# ir-sensor-breakout-mk-3_0-pth.net
KiCad netlist of a schematic drawn in EAGLE
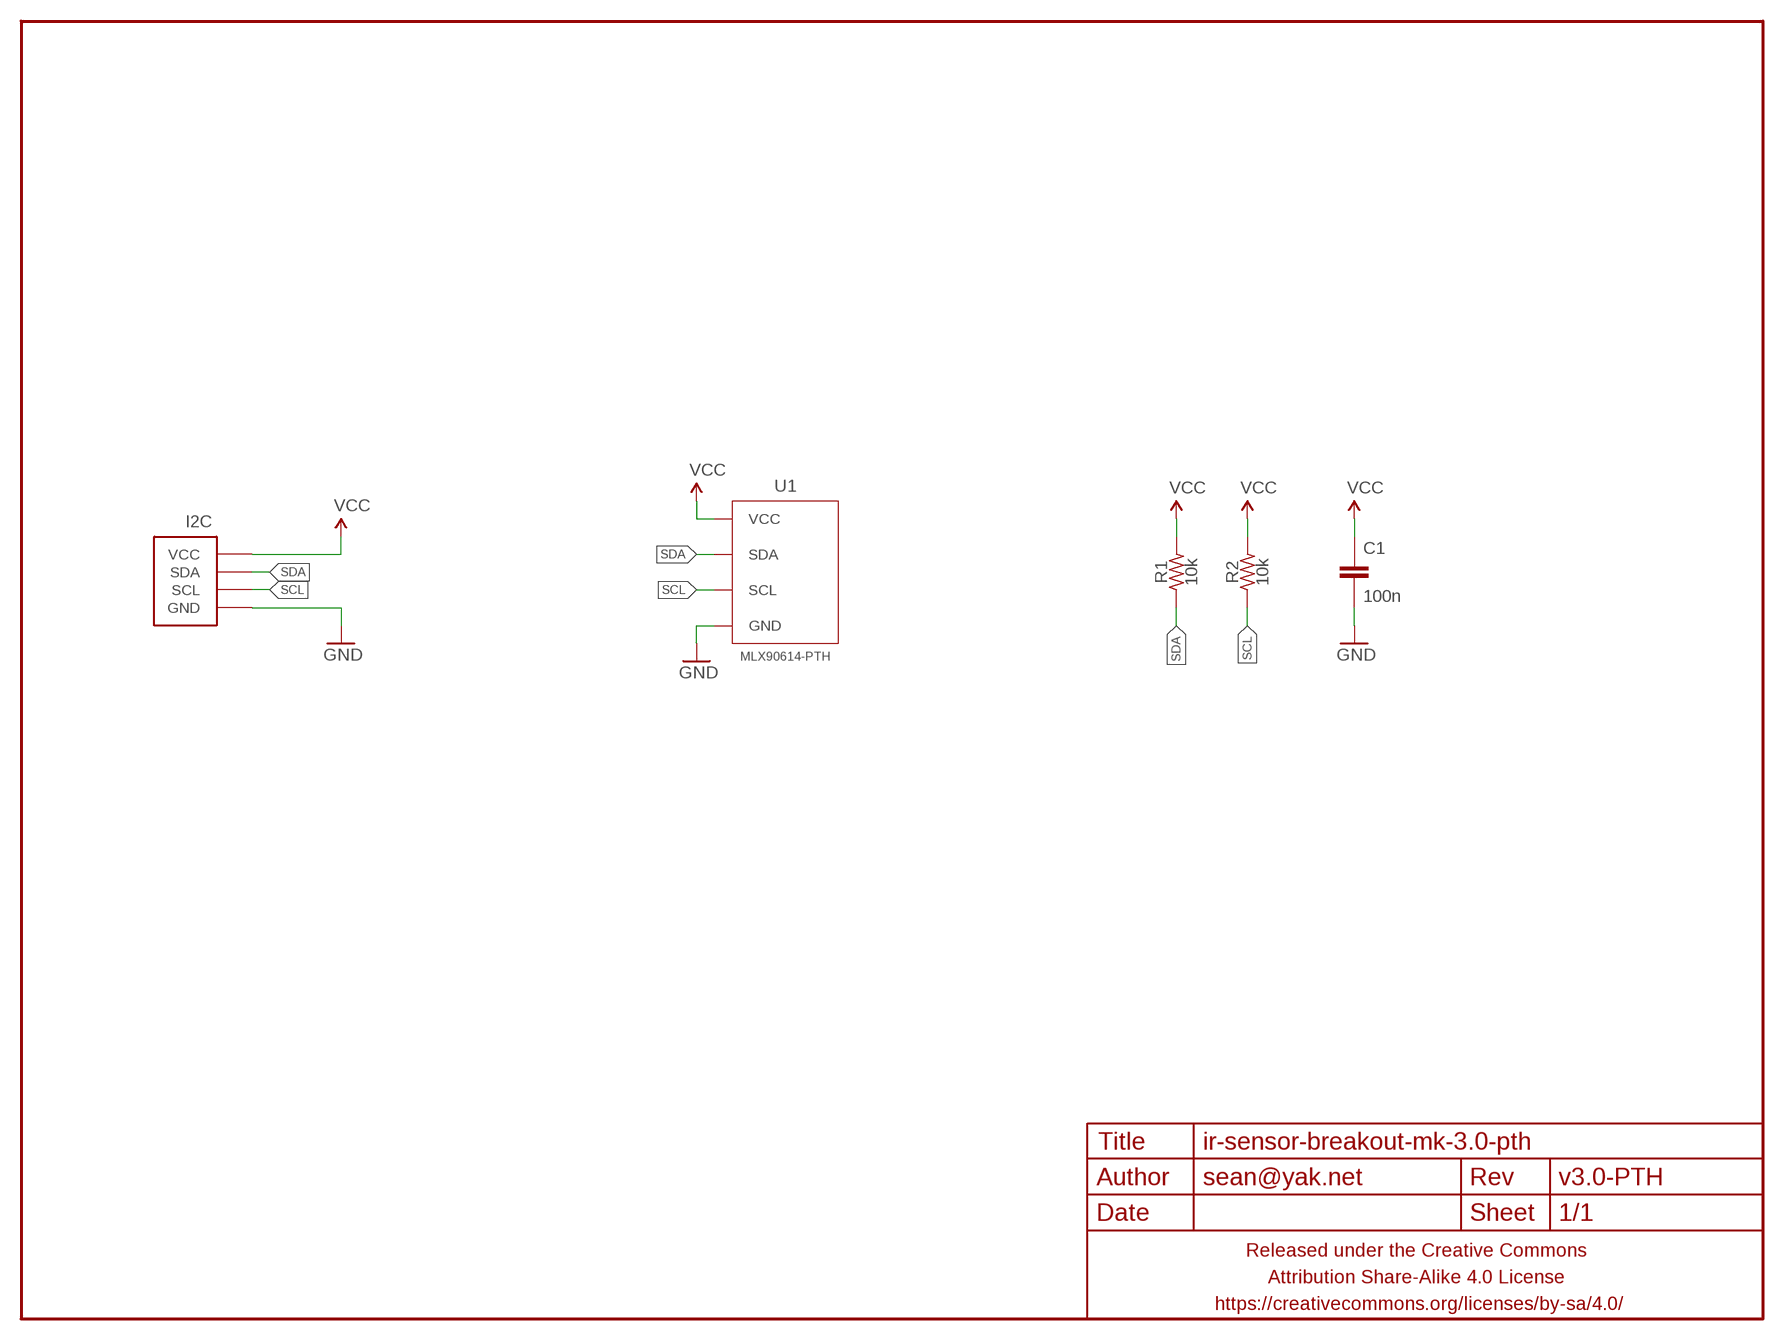
[diagram p0: schematic, sheet 1]

(export (version "E")
  (design (tool "Eeschema 10.0.6"))
  (components
    (comp (ref "C1")
      (value "100n")
      (footprint "eagle-import:C025-024X044")
      (libsource (lib "eagle-import") (part "CAPACITOR-CERAMIC025-024X044"))
    )
    (comp (ref "FRAME1")
      (value "FRAME-LETTERNO_PACKAGE")
      (footprint "eagle-import:DUMMY")
      (fields (field (name "DESIGNER") "sean@yak.net") (field (name "VERSION") "v3.0-PTH"))
      (libsource (lib "eagle-import") (part "FRAME-LETTERNO_PACKAGE"))
    )
    (comp (ref "I2C")
      (value "M04-I2CPTH-0.1IN-CENTERED-FLIPPED")
      (footprint "eagle-import:1X04-PTH-VERT-I2C-CENTERED-FLIPPED")
      (libsource (lib "eagle-import") (part "M04-I2CPTH-0.1IN-CENTERED-FLIPPED"))
    )
    (comp (ref "R1")
      (value "10k")
      (footprint "eagle-import:RESISTOR-AXIAL-PTH-5.08MM")
      (libsource (lib "eagle-import") (part "RESISTORPTH-AXIAL-5.08MM"))
    )
    (comp (ref "R2")
      (value "10k")
      (footprint "eagle-import:RESISTOR-AXIAL-PTH-5.08MM")
      (libsource (lib "eagle-import") (part "RESISTORPTH-AXIAL-5.08MM"))
    )
    (comp (ref "U1")
      (value "MLX90614-PTH")
      (footprint "eagle-import:TO-39-4")
      (libsource (lib "eagle-import") (part "MLX906145V-PTH"))
    )
  )
  (nets
    (net (code "1") (name "GND") (class "Default")
      (node (ref "C1") (pin "2") (pinfunction "2_2") (pintype "passive"))
      (node (ref "I2C") (pin "GND") (pinfunction "GND_GND") (pintype "bidirectional"))
      (node (ref "U1") (pin "4") (pinfunction "GND_4") (pintype "bidirectional"))
    )
    (net (code "2") (name "SCL") (class "Default")
      (node (ref "I2C") (pin "SCL") (pinfunction "SCL_SCL") (pintype "bidirectional"))
      (node (ref "R2") (pin "P$1") (pinfunction "1_P$1") (pintype "passive"))
      (node (ref "U1") (pin "1") (pinfunction "SCL_1") (pintype "bidirectional"))
    )
    (net (code "3") (name "SDA") (class "Default")
      (node (ref "I2C") (pin "SDA") (pinfunction "SDA_SDA") (pintype "bidirectional"))
      (node (ref "R1") (pin "P$1") (pinfunction "1_P$1") (pintype "passive"))
      (node (ref "U1") (pin "2") (pinfunction "SDA_2") (pintype "bidirectional"))
    )
    (net (code "4") (name "VCC") (class "Default")
      (node (ref "C1") (pin "1") (pinfunction "1_1") (pintype "passive"))
      (node (ref "I2C") (pin "VCC") (pinfunction "VCC_VCC") (pintype "bidirectional"))
      (node (ref "R1") (pin "P$2") (pinfunction "2_P$2") (pintype "passive"))
      (node (ref "R2") (pin "P$2") (pinfunction "2_P$2") (pintype "passive"))
      (node (ref "U1") (pin "3") (pinfunction "VCC_3") (pintype "bidirectional"))
    )
  )
)
